# LDO-Schematic.net
KiCad netlist of a schematic drawn in Altium Designer
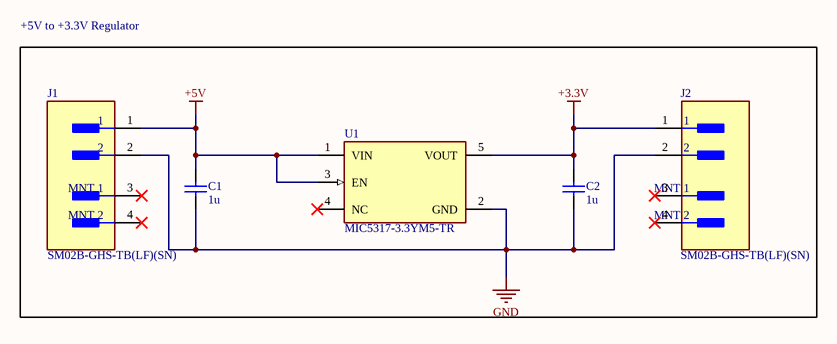
[diagram p0: LDO-Schematic.SchDoc]

(export (version "E")
  (design (tool "Eeschema 10.0.6"))
  (components
    (comp (ref "C1")
      (value "1u")
      (footprint "CAPC2013X100X50ML20T25")
      (fields (field (name "PART NUMBER") "C0805C105K8RACTU") (field (name "MANUFACTURER") "Kemet"))
      (libsource (lib "Altium Content Vault") (part "CAP"))
    )
    (comp (ref "C2")
      (value "1u")
      (footprint "CAPC2013X100X50ML20T25")
      (fields (field (name "PART NUMBER") "C0805C105K8RACTU") (field (name "MANUFACTURER") "Kemet"))
      (libsource (lib "Altium Content Vault") (part "CAP"))
    )
    (comp (ref "J1")
      (value "SM02B-GHS-TB(LF)(SN)")
      (footprint "FP-SM02B-GHS-TB_LF_SN-MFG")
      (description "CONN HEADER SMD R/A 2POS 1.25MM")
      (libsource (lib "") (part "56ec3178a87b3978bdc1b3682cd516a_1"))
    )
    (comp (ref "J2")
      (value "SM02B-GHS-TB(LF)(SN)")
      (footprint "FP-SM02B-GHS-TB_LF_SN-MFG")
      (description "CONN HEADER SMD R/A 2POS 1.25MM")
      (libsource (lib "Altium Content Vault") (part "56ec3178a87b3978bdc1b3682cd516a"))
    )
    (comp (ref "U1")
      (value "MIC5317-3.3YM5-TR")
      (footprint "FP-SOT23-5LD-PL-1-MFG")
      (description "IC REG LINEAR 3.3V 150MA SOT23-5")
      (libsource (lib "Altium Content Vault") (part "0a093dae7315cdc977fd108dde87457"))
    )
  )
  (nets
    (net (code "1") (name "+3.3V") (class "Default")
      (node (ref "C2") (pin "2") (pinfunction "2_2") (pintype "passive"))
      (node (ref "J2") (pin "1") (pinfunction "1_1") (pintype "passive"))
      (node (ref "U1") (pin "5") (pinfunction "VOUT_5") (pintype "power_in"))
    )
    (net (code "2") (name "+5V") (class "Default")
      (node (ref "C1") (pin "2") (pinfunction "2_2") (pintype "passive"))
      (node (ref "J1") (pin "1") (pinfunction "1_1") (pintype "passive"))
      (node (ref "U1") (pin "1") (pinfunction "VIN_1") (pintype "power_in"))
      (node (ref "U1") (pin "3") (pinfunction "EN_3") (pintype "input"))
    )
    (net (code "3") (name "GND") (class "Default")
      (node (ref "C1") (pin "1") (pinfunction "1_1") (pintype "passive"))
      (node (ref "C2") (pin "1") (pinfunction "1_1") (pintype "passive"))
      (node (ref "J1") (pin "2") (pinfunction "2_2") (pintype "passive"))
      (node (ref "J2") (pin "2") (pinfunction "2_2") (pintype "passive"))
      (node (ref "U1") (pin "2") (pinfunction "GND_2") (pintype "power_in"))
    )
    (net (code "4") (name "unconnected-(J1-MNT_1-Pad3)") (class "Default")
      (node (ref "J1") (pin "3") (pinfunction "MNT_1_3") (pintype "passive+no_connect"))
    )
    (net (code "5") (name "unconnected-(J1-MNT_2-Pad4)") (class "Default")
      (node (ref "J1") (pin "4") (pinfunction "MNT_2_4") (pintype "passive+no_connect"))
    )
    (net (code "6") (name "unconnected-(J2-MNT_1-Pad3)") (class "Default")
      (node (ref "J2") (pin "3") (pinfunction "MNT_1_3") (pintype "passive+no_connect"))
    )
    (net (code "7") (name "unconnected-(J2-MNT_2-Pad4)") (class "Default")
      (node (ref "J2") (pin "4") (pinfunction "MNT_2_4") (pintype "passive+no_connect"))
    )
    (net (code "8") (name "unconnected-(U1-NC-Pad4)") (class "Default")
      (node (ref "U1") (pin "4") (pinfunction "NC_4") (pintype "passive+no_connect"))
    )
  )
)
